# PowerDelivery.net
KiCad netlist of a schematic drawn in Altium Designer
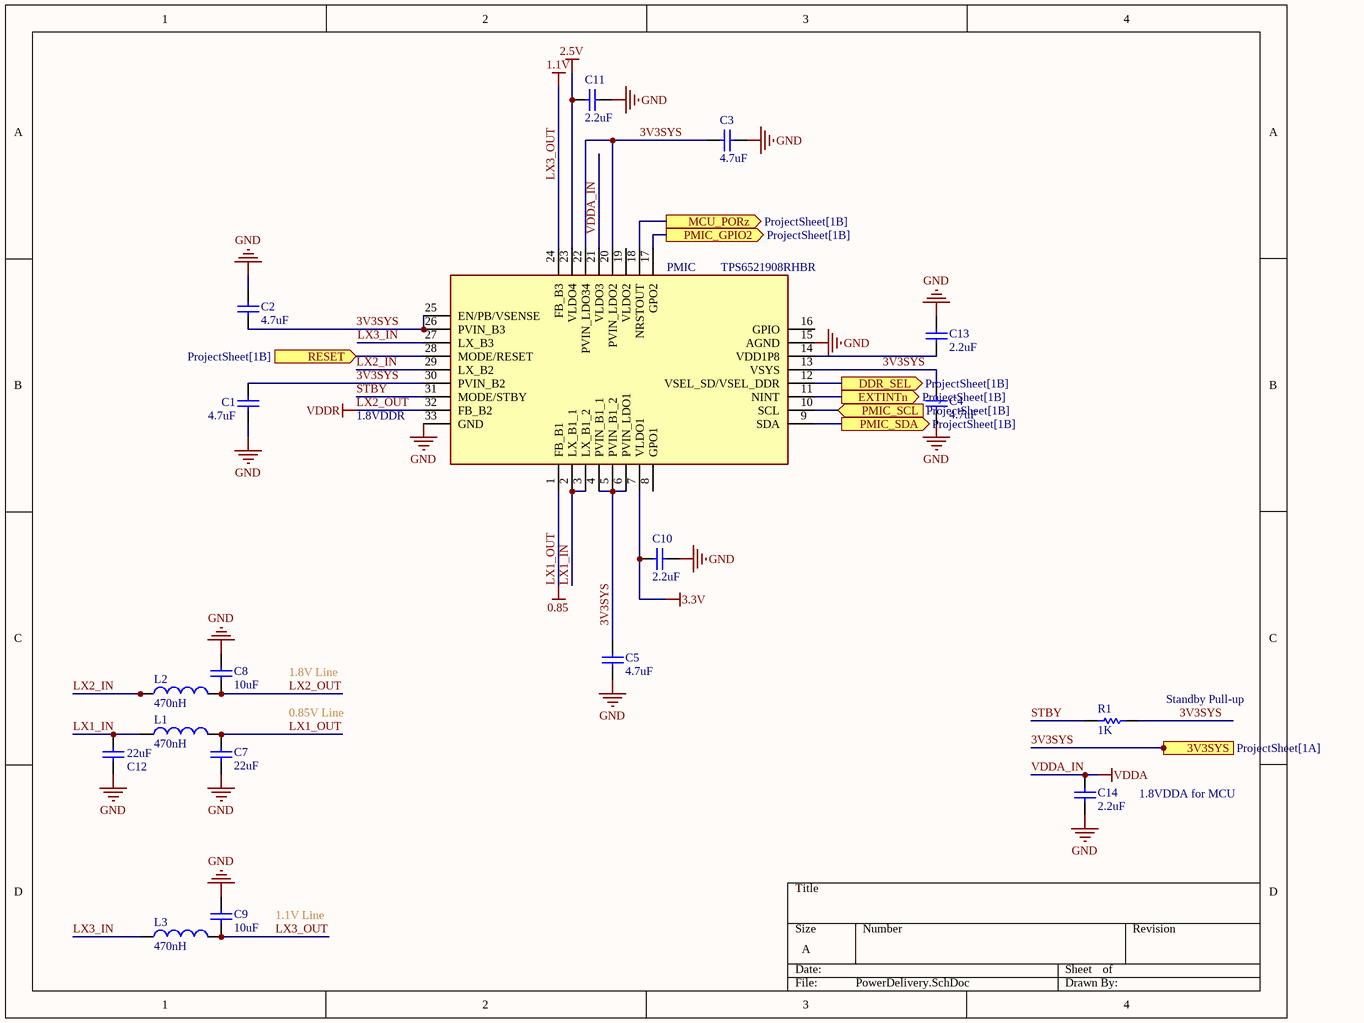
[diagram p0: PowerDelivery.SchDoc]

(export (version "E")
  (design (tool "Eeschema 10.0.6"))
  (components
    (comp (ref "C1")
      (value "4.7uF")
      (description "Capacitor")
      (libsource (lib "Simulation Generic Components") (part "Capacitor"))
    )
    (comp (ref "C2")
      (value "4.7uF")
      (description "Capacitor")
      (libsource (lib "Simulation Generic Components") (part "Capacitor"))
    )
    (comp (ref "C3")
      (value "4.7uF")
      (description "Capacitor")
      (libsource (lib "Simulation Generic Components") (part "Capacitor"))
    )
    (comp (ref "C4")
      (value "4.7uF")
      (description "Capacitor")
      (libsource (lib "Simulation Generic Components") (part "Capacitor"))
    )
    (comp (ref "C5")
      (value "4.7uF")
      (description "Capacitor")
      (libsource (lib "Simulation Generic Components") (part "Capacitor"))
    )
    (comp (ref "C7")
      (value "22uF")
      (description "Capacitor")
      (libsource (lib "Simulation Generic Components") (part "Capacitor"))
    )
    (comp (ref "C8")
      (value "10uF")
      (description "Capacitor")
      (libsource (lib "Simulation Generic Components") (part "Capacitor"))
    )
    (comp (ref "C9")
      (value "10uF")
      (description "Capacitor")
      (libsource (lib "Simulation Generic Components") (part "Capacitor"))
    )
    (comp (ref "C10")
      (value "2.2uF")
      (description "Capacitor")
      (libsource (lib "Simulation Generic Components") (part "Capacitor"))
    )
    (comp (ref "C11")
      (value "2.2uF")
      (description "Capacitor")
      (libsource (lib "Simulation Generic Components") (part "Capacitor"))
    )
    (comp (ref "C12")
      (value "22uF")
      (description "Capacitor")
      (libsource (lib "Simulation Generic Components") (part "Capacitor"))
    )
    (comp (ref "C13")
      (value "2.2uF")
      (description "Capacitor")
      (libsource (lib "Simulation Generic Components") (part "Capacitor"))
    )
    (comp (ref "C14")
      (value "2.2uF")
      (description "Capacitor")
      (libsource (lib "Simulation Generic Components") (part "Capacitor"))
    )
    (comp (ref "L1")
      (value "470nH")
      (description "Inductor")
      (libsource (lib "Simulation Generic Components") (part "Inductor"))
    )
    (comp (ref "L2")
      (value "470nH")
      (description "Inductor")
      (libsource (lib "Simulation Generic Components") (part "Inductor"))
    )
    (comp (ref "L3")
      (value "470nH")
      (description "Inductor")
      (libsource (lib "Simulation Generic Components") (part "Inductor"))
    )
    (comp (ref "PMIC")
      (value "TPS6521908RHBR")
      (footprint "SamacSys:QFN50P500X500X100-33N-D")
      (description "Power Management Integrated Circuit")
      (fields (field (name "MOUSER PART NUMBER") "595-TPS6521908RHBR"))
      (libsource (lib "*") (part "TPS6521908RHBR"))
    )
    (comp (ref "R1")
      (value "1K")
      (description "Resistor")
      (libsource (lib "Simulation Generic Components") (part "Resistor"))
    )
  )
  (nets
    (net (code "1") (name "/3V3SYS") (class "Default")
      (node (ref "C1") (pin "2") (pinfunction "2_2") (pintype "passive"))
      (node (ref "C2") (pin "2") (pinfunction "2_2") (pintype "passive"))
      (node (ref "C3") (pin "1") (pinfunction "1_1") (pintype "passive"))
      (node (ref "C4") (pin "1") (pinfunction "1_1") (pintype "passive"))
      (node (ref "C5") (pin "2") (pinfunction "2_2") (pintype "passive"))
      (node (ref "PMIC") (pin "13") (pinfunction "VSYS_13") (pintype "passive"))
      (node (ref "PMIC") (pin "20") (pinfunction "PVIN_LDO2_20") (pintype "passive"))
      (node (ref "PMIC") (pin "22") (pinfunction "PVIN_LDO34_22") (pintype "passive"))
      (node (ref "PMIC") (pin "25") (pinfunction "EN/PB/VSENSE_25") (pintype "passive"))
      (node (ref "PMIC") (pin "26") (pinfunction "PVIN_B3_26") (pintype "passive"))
      (node (ref "PMIC") (pin "30") (pinfunction "PVIN_B2_30") (pintype "passive"))
      (node (ref "PMIC") (pin "4") (pinfunction "PVIN_B1_1_4") (pintype "passive"))
      (node (ref "PMIC") (pin "5") (pinfunction "PVIN_B1_2_5") (pintype "passive"))
      (node (ref "PMIC") (pin "6") (pinfunction "PVIN_LDO1_6") (pintype "passive"))
      (node (ref "R1") (pin "2") (pinfunction "2_2") (pintype "passive"))
    )
    (net (code "2") (name "/DDR_SEL") (class "Default")
      (node (ref "PMIC") (pin "12") (pinfunction "VSEL_SD/VSEL_DDR_12") (pintype "passive"))
    )
    (net (code "3") (name "/EXTINTn") (class "Default")
      (node (ref "PMIC") (pin "11") (pinfunction "NINT_11") (pintype "passive"))
    )
    (net (code "4") (name "/LX1_IN") (class "Default")
      (node (ref "C12") (pin "2") (pinfunction "2_2") (pintype "passive"))
      (node (ref "L1") (pin "1") (pinfunction "1_1") (pintype "passive"))
      (node (ref "PMIC") (pin "2") (pinfunction "LX_B1_1_2") (pintype "passive"))
      (node (ref "PMIC") (pin "3") (pinfunction "LX_B1_2_3") (pintype "passive"))
    )
    (net (code "5") (name "/LX2_IN") (class "Default")
      (node (ref "L2") (pin "1") (pinfunction "1_1") (pintype "passive"))
      (node (ref "PMIC") (pin "29") (pinfunction "LX_B2_29") (pintype "passive"))
    )
    (net (code "6") (name "/LX3_IN") (class "Default")
      (node (ref "L3") (pin "1") (pinfunction "1_1") (pintype "passive"))
      (node (ref "PMIC") (pin "27") (pinfunction "LX_B3_27") (pintype "passive"))
    )
    (net (code "7") (name "/MCU_PORz") (class "Default")
      (node (ref "PMIC") (pin "18") (pinfunction "NRSTOUT_18") (pintype "passive"))
    )
    (net (code "8") (name "/PMIC_GPIO2") (class "Default")
      (node (ref "PMIC") (pin "17") (pinfunction "GPO2_17") (pintype "passive"))
    )
    (net (code "9") (name "/PMIC_SCL") (class "Default")
      (node (ref "PMIC") (pin "10") (pinfunction "SCL_10") (pintype "passive"))
    )
    (net (code "10") (name "/PMIC_SDA") (class "Default")
      (node (ref "PMIC") (pin "9") (pinfunction "SDA_9") (pintype "passive"))
    )
    (net (code "11") (name "/RESET") (class "Default")
      (node (ref "PMIC") (pin "28") (pinfunction "MODE/RESET_28") (pintype "passive"))
    )
    (net (code "12") (name "/STBY") (class "Default")
      (node (ref "PMIC") (pin "31") (pinfunction "MODE/STBY_31") (pintype "passive"))
      (node (ref "R1") (pin "1") (pinfunction "1_1") (pintype "passive"))
    )
    (net (code "13") (name "0.85") (class "Default")
      (node (ref "C7") (pin "2") (pinfunction "2_2") (pintype "passive"))
      (node (ref "L1") (pin "2") (pinfunction "2_2") (pintype "passive"))
      (node (ref "PMIC") (pin "1") (pinfunction "FB_B1_1") (pintype "passive"))
    )
    (net (code "14") (name "1.1V") (class "Default")
      (node (ref "C9") (pin "2") (pinfunction "2_2") (pintype "passive"))
      (node (ref "L3") (pin "2") (pinfunction "2_2") (pintype "passive"))
      (node (ref "PMIC") (pin "24") (pinfunction "FB_B3_24") (pintype "passive"))
    )
    (net (code "15") (name "2.5V") (class "Default")
      (node (ref "C11") (pin "1") (pinfunction "1_1") (pintype "passive"))
      (node (ref "PMIC") (pin "23") (pinfunction "VLDO4_23") (pintype "passive"))
    )
    (net (code "16") (name "3.3V") (class "Default")
      (node (ref "C10") (pin "2") (pinfunction "2_2") (pintype "passive"))
      (node (ref "PMIC") (pin "7") (pinfunction "VLDO1_7") (pintype "passive"))
    )
    (net (code "17") (name "GND") (class "Default")
      (node (ref "C1") (pin "1") (pinfunction "1_1") (pintype "passive"))
      (node (ref "C10") (pin "1") (pinfunction "1_1") (pintype "passive"))
      (node (ref "C11") (pin "2") (pinfunction "2_2") (pintype "passive"))
      (node (ref "C12") (pin "1") (pinfunction "1_1") (pintype "passive"))
      (node (ref "C13") (pin "2") (pinfunction "2_2") (pintype "passive"))
      (node (ref "C14") (pin "1") (pinfunction "1_1") (pintype "passive"))
      (node (ref "C2") (pin "1") (pinfunction "1_1") (pintype "passive"))
      (node (ref "C3") (pin "2") (pinfunction "2_2") (pintype "passive"))
      (node (ref "C4") (pin "2") (pinfunction "2_2") (pintype "passive"))
      (node (ref "C5") (pin "1") (pinfunction "1_1") (pintype "passive"))
      (node (ref "C7") (pin "1") (pinfunction "1_1") (pintype "passive"))
      (node (ref "C8") (pin "1") (pinfunction "1_1") (pintype "passive"))
      (node (ref "C9") (pin "1") (pinfunction "1_1") (pintype "passive"))
      (node (ref "PMIC") (pin "15") (pinfunction "AGND_15") (pintype "passive"))
      (node (ref "PMIC") (pin "33") (pinfunction "GND_33") (pintype "passive"))
    )
    (net (code "18") (name "Net-(PMIC-VDD1P8)") (class "Default")
      (node (ref "C13") (pin "1") (pinfunction "1_1") (pintype "passive"))
      (node (ref "PMIC") (pin "14") (pinfunction "VDD1P8_14") (pintype "passive"))
    )
    (net (code "19") (name "VDDA") (class "Default")
      (node (ref "C14") (pin "2") (pinfunction "2_2") (pintype "passive"))
      (node (ref "PMIC") (pin "21") (pinfunction "VLDO3_21") (pintype "passive"))
    )
    (net (code "20") (name "VDDR") (class "Default")
      (node (ref "C8") (pin "2") (pinfunction "2_2") (pintype "passive"))
      (node (ref "L2") (pin "2") (pinfunction "2_2") (pintype "passive"))
      (node (ref "PMIC") (pin "32") (pinfunction "FB_B2_32") (pintype "passive"))
    )
    (net (code "21") (name "unconnected-(PMIC-GPIO-Pad16)") (class "Default")
      (node (ref "PMIC") (pin "16") (pinfunction "GPIO_16") (pintype "passive"))
    )
    (net (code "22") (name "unconnected-(PMIC-GPO1-Pad8)") (class "Default")
      (node (ref "PMIC") (pin "8") (pinfunction "GPO1_8") (pintype "passive"))
    )
    (net (code "23") (name "unconnected-(PMIC-VLDO2-Pad19)") (class "Default")
      (node (ref "PMIC") (pin "19") (pinfunction "VLDO2_19") (pintype "passive"))
    )
  )
)
